# Power_logger_diy_current_voltage_sensors.net
KiCad netlist of a schematic drawn in EasyEDA
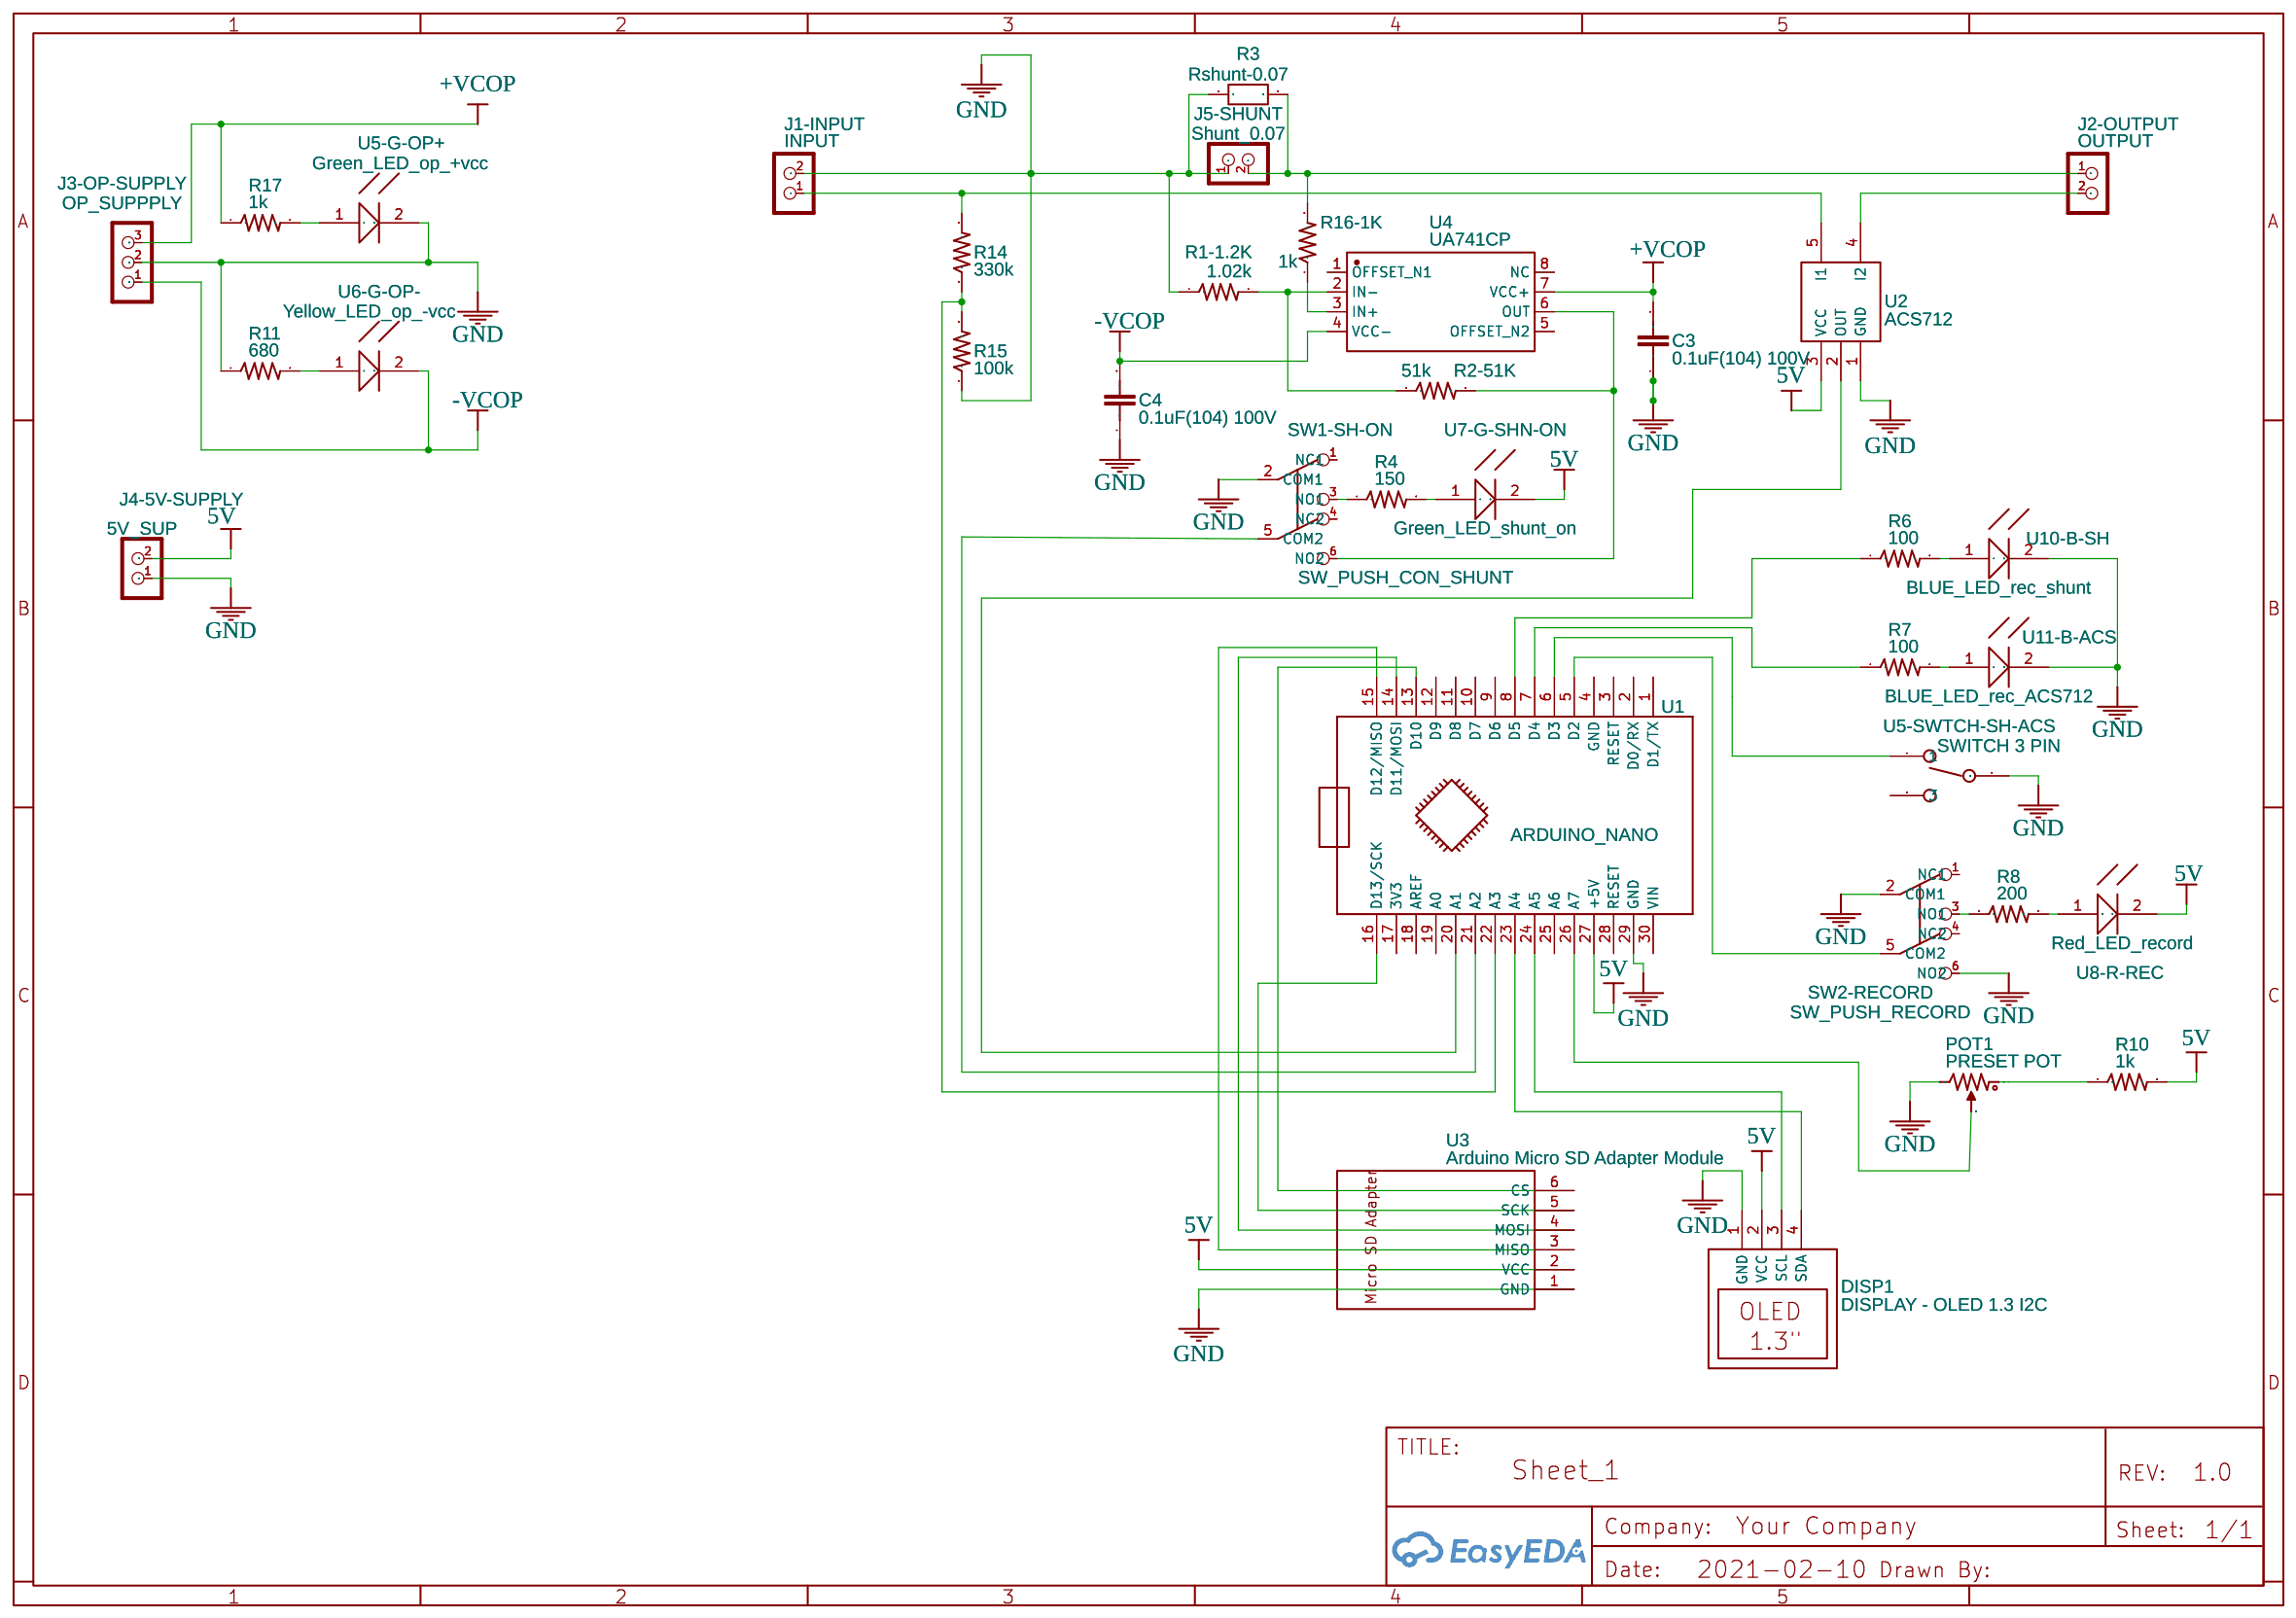
[diagram p0: schematic sheet]

(export (version "E")
  (design (tool "Eeschema 10.0.6"))
  (components
    (comp (ref "C3")
      (value "0.1uF(104) 100V")
      (fields (field (name "BOM_Manufacturer Part") "?"))
      (libsource (lib "") (part "Capacitor Ceramic TH 0.1"))
    )
    (comp (ref "C4")
      (value "0.1uF(104) 100V")
      (fields (field (name "BOM_Manufacturer Part") "?"))
      (libsource (lib "") (part "Capacitor Ceramic TH 0.1"))
    )
    (comp (ref "DISP1") (value "DISPLAY - OLED 1.3 I2C") (libsource (lib "") (part "DISPLAY - OLED 1.3 I2C")))
    (comp (ref "J1-INPUT") (value "INPUT") (libsource (lib "") (part "CON_TERMINAL_BLOCK_02_1")))
    (comp (ref "J2-OUTPUT") (value "OUTPUT") (libsource (lib "") (part "CON_TERMINAL_BLOCK_02_2")))
    (comp (ref "J3-OP-SUPPLY") (value "OP_SUPPPLY") (libsource (lib "") (part "CON_TERMINAL_BLOCK_03")))
    (comp (ref "J4-5V-SUPPLY") (value "5V_SUP") (libsource (lib "") (part "CON_TERMINAL_BLOCK_02_3")))
    (comp (ref "J5-SHUNT") (value "Shunt_0.07") (libsource (lib "") (part "CON_TERMINAL_BLOCK_02")))
    (comp (ref "POT1") (value "PRESET POT") (libsource (lib "") (part "PRESET POT")))
    (comp (ref "R1-1.2K") (value "1.02k") (libsource (lib "") (part "RESISTORKIT_2")))
    (comp (ref "R2-51K") (value "51k") (libsource (lib "") (part "RESISTORKIT_3")))
    (comp (ref "R3") (value "Rshunt-0.07") (libsource (lib "") (part "Res_AXIAL-1.0(3W)_EU")))
    (comp (ref "R4") (value "150") (libsource (lib "") (part "RESISTORKIT")))
    (comp (ref "R6") (value "100") (libsource (lib "") (part "RESISTORKIT")))
    (comp (ref "R7") (value "100") (libsource (lib "") (part "RESISTORKIT")))
    (comp (ref "R8") (value "200") (libsource (lib "") (part "RESISTORKIT")))
    (comp (ref "R10") (value "1k") (libsource (lib "") (part "RESISTORKIT")))
    (comp (ref "R11") (value "680") (libsource (lib "") (part "RESISTORKIT")))
    (comp (ref "R14") (value "330k") (libsource (lib "") (part "RESISTORKIT_1")))
    (comp (ref "R15") (value "100k") (libsource (lib "") (part "RESISTORKIT_1")))
    (comp (ref "R16-1K") (value "1k") (libsource (lib "") (part "RESISTORKIT_4")))
    (comp (ref "R17") (value "1k") (libsource (lib "") (part "RESISTORKIT")))
    (comp (ref "SW1-SH-ON") (value "SW_PUSH_CON_SHUNT") (libsource (lib "") (part "SW_PUSH_DPDT_1")))
    (comp (ref "SW2-RECORD") (value "SW_PUSH_RECORD") (libsource (lib "") (part "SW_PUSH_DPDT")))
    (comp (ref "U1") (value "ARDUINO_NANO") (libsource (lib "") (part "ARDUINO_NANO")))
    (comp (ref "U2") (value "ACS712") (libsource (lib "") (part "ACS712")))
    (comp (ref "U3")
      (value "Arduino Micro SD Adapter Module")
      (libsource (lib "") (part "Arduino Micro SD Adapter Module"))
    )
    (comp (ref "U4")
      (value "UA741CP")
      (fields (field (name "BOM_Supplier Part") "C78758"))
      (libsource (lib "") (part "UA741CP"))
    )
    (comp (ref "U5-G-OP+")
      (value "Green_LED_op_+vcc")
      (fields (field (name "BOM_Manufacturer Part") "703-0090") (field (name "BOM_Supplier Part") "2112100"))
      (libsource (lib "") (part "Red LED"))
    )
    (comp (ref "U5-SWTCH-SH-ACS")
      (value "SWITCH 3 PIN")
      (fields
        (field (name "BOM_Manufacturer Part") "SWITCH")
        (field (name "BOM_Supplier Part") "SWITCH symbol")
      )
      (libsource (lib "") (part "SWITCH 3 PIN"))
    )
    (comp (ref "U6-G-OP-")
      (value "Yellow_LED_op_-vcc")
      (fields (field (name "BOM_Manufacturer Part") "703-0090") (field (name "BOM_Supplier Part") "2112100"))
      (libsource (lib "") (part "Red LED_4"))
    )
    (comp (ref "U7-G-SHN-ON")
      (value "Green_LED_shunt_on")
      (fields (field (name "BOM_Manufacturer Part") "703-0090") (field (name "BOM_Supplier Part") "2112100"))
      (libsource (lib "") (part "Red LED_3"))
    )
    (comp (ref "U8-R-REC")
      (value "Red_LED_record")
      (fields (field (name "BOM_Manufacturer Part") "703-0090") (field (name "BOM_Supplier Part") "2112100"))
      (libsource (lib "") (part "Red LED_1"))
    )
    (comp (ref "U10-B-SH")
      (value "BLUE_LED_rec_shunt")
      (fields (field (name "BOM_Manufacturer Part") "703-0090") (field (name "BOM_Supplier Part") "2112100"))
      (libsource (lib "") (part "Red LED_2"))
    )
    (comp (ref "U11-B-ACS")
      (value "BLUE_LED_rec_ACS712")
      (fields (field (name "BOM_Manufacturer Part") "703-0090") (field (name "BOM_Supplier Part") "2112100"))
      (libsource (lib "") (part "Red LED_5"))
    )
  )
  (nets
    (net (code "1") (name "+VCOP") (class "Default")
      (node (ref "C3") (pin "2") (pinfunction "2_2") (pintype "unspecified"))
      (node (ref "J3-OP-SUPPLY") (pin "3") (pinfunction "3_3") (pintype "unspecified"))
      (node (ref "R17") (pin "1") (pinfunction "1_1") (pintype "unspecified"))
      (node (ref "U4") (pin "7") (pinfunction "VCC+_7") (pintype "unspecified"))
    )
    (net (code "2") (name "-VCOP") (class "Default")
      (node (ref "C4") (pin "2") (pinfunction "2_2") (pintype "unspecified"))
      (node (ref "J3-OP-SUPPLY") (pin "1") (pinfunction "1_1") (pintype "unspecified"))
      (node (ref "U4") (pin "4") (pinfunction "VCC-_4") (pintype "unspecified"))
      (node (ref "U6-G-OP-") (pin "2") (pinfunction "2_2") (pintype "unspecified"))
    )
    (net (code "3") (name "5V") (class "Default")
      (node (ref "DISP1") (pin "2") (pinfunction "VCC_2") (pintype "bidirectional"))
      (node (ref "J4-5V-SUPPLY") (pin "2") (pinfunction "2_2") (pintype "unspecified"))
      (node (ref "R10") (pin "2") (pinfunction "2_2") (pintype "unspecified"))
      (node (ref "U1") (pin "27") (pinfunction "+5V_27") (pintype "unspecified"))
      (node (ref "U2") (pin "3") (pinfunction "VCC_3") (pintype "unspecified"))
      (node (ref "U3") (pin "2") (pinfunction "VCC_2") (pintype "unspecified"))
      (node (ref "U7-G-SHN-ON") (pin "2") (pinfunction "2_2") (pintype "unspecified"))
      (node (ref "U8-R-REC") (pin "2") (pinfunction "2_2") (pintype "unspecified"))
    )
    (net (code "4") (name "GND") (class "Default")
      (node (ref "C3") (pin "1") (pinfunction "1_1") (pintype "unspecified"))
      (node (ref "C4") (pin "1") (pinfunction "1_1") (pintype "unspecified"))
      (node (ref "DISP1") (pin "1") (pinfunction "GND_1") (pintype "bidirectional"))
      (node (ref "J1-INPUT") (pin "2") (pinfunction "2_2") (pintype "unspecified"))
      (node (ref "J3-OP-SUPPLY") (pin "2") (pinfunction "2_2") (pintype "unspecified"))
      (node (ref "J4-5V-SUPPLY") (pin "1") (pinfunction "1_1") (pintype "unspecified"))
      (node (ref "J5-SHUNT") (pin "1") (pinfunction "1_1") (pintype "unspecified"))
      (node (ref "POT1") (pin "3") (pinfunction "3_3") (pintype "unspecified"))
      (node (ref "R1-1.2K") (pin "1") (pinfunction "1_1") (pintype "unspecified"))
      (node (ref "R11") (pin "1") (pinfunction "1_1") (pintype "unspecified"))
      (node (ref "R15") (pin "1") (pinfunction "1_1") (pintype "unspecified"))
      (node (ref "R3") (pin "1") (pinfunction "1_1") (pintype "unspecified"))
      (node (ref "SW1-SH-ON") (pin "2") (pinfunction "COM1_2") (pintype "unspecified"))
      (node (ref "SW2-RECORD") (pin "2") (pinfunction "COM1_2") (pintype "unspecified"))
      (node (ref "SW2-RECORD") (pin "6") (pinfunction "NO2_6") (pintype "unspecified"))
      (node (ref "U1") (pin "29") (pinfunction "GND_29") (pintype "unspecified"))
      (node (ref "U10-B-SH") (pin "2") (pinfunction "2_2") (pintype "unspecified"))
      (node (ref "U11-B-ACS") (pin "2") (pinfunction "2_2") (pintype "unspecified"))
      (node (ref "U2") (pin "1") (pinfunction "GND_1") (pintype "unspecified"))
      (node (ref "U3") (pin "1") (pinfunction "GND_1") (pintype "unspecified"))
      (node (ref "U5-G-OP+") (pin "2") (pinfunction "2_2") (pintype "unspecified"))
      (node (ref "U5-SWTCH-SH-ACS") (pin "2") (pinfunction "2_2") (pintype "unspecified"))
    )
    (net (code "5") (name "Net-(DISP1-SCL)") (class "Default")
      (node (ref "DISP1") (pin "3") (pinfunction "SCL_3") (pintype "passive"))
      (node (ref "U1") (pin "24") (pinfunction "A5_24") (pintype "unspecified"))
    )
    (net (code "6") (name "Net-(DISP1-SDA)") (class "Default")
      (node (ref "DISP1") (pin "4") (pinfunction "SDA_4") (pintype "passive"))
      (node (ref "U1") (pin "23") (pinfunction "A4_23") (pintype "unspecified"))
    )
    (net (code "7") (name "Net-(J2-OUTPUT-Pad1)") (class "Default")
      (node (ref "J2-OUTPUT") (pin "1") (pinfunction "1_1") (pintype "unspecified"))
      (node (ref "J5-SHUNT") (pin "2") (pinfunction "2_2") (pintype "unspecified"))
      (node (ref "R16-1K") (pin "2") (pinfunction "2_2") (pintype "unspecified"))
      (node (ref "R3") (pin "2") (pinfunction "2_2") (pintype "unspecified"))
    )
    (net (code "8") (name "Net-(POT1-Pad1)") (class "Default")
      (node (ref "POT1") (pin "1") (pinfunction "1_1") (pintype "unspecified"))
      (node (ref "R10") (pin "1") (pinfunction "1_1") (pintype "unspecified"))
    )
    (net (code "9") (name "Net-(R4-Pad2)") (class "Default")
      (node (ref "R4") (pin "2") (pinfunction "2_2") (pintype "unspecified"))
      (node (ref "U7-G-SHN-ON") (pin "1") (pinfunction "1_1") (pintype "unspecified"))
    )
    (net (code "10") (name "Net-(R6-Pad2)") (class "Default")
      (node (ref "R6") (pin "2") (pinfunction "2_2") (pintype "unspecified"))
      (node (ref "U10-B-SH") (pin "1") (pinfunction "1_1") (pintype "unspecified"))
    )
    (net (code "11") (name "Net-(R7-Pad2)") (class "Default")
      (node (ref "R7") (pin "2") (pinfunction "2_2") (pintype "unspecified"))
      (node (ref "U11-B-ACS") (pin "1") (pinfunction "1_1") (pintype "unspecified"))
    )
    (net (code "12") (name "Net-(R8-Pad2)") (class "Default")
      (node (ref "R8") (pin "2") (pinfunction "2_2") (pintype "unspecified"))
      (node (ref "U8-R-REC") (pin "1") (pinfunction "1_1") (pintype "unspecified"))
    )
    (net (code "13") (name "Net-(R11-Pad2)") (class "Default")
      (node (ref "R11") (pin "2") (pinfunction "2_2") (pintype "unspecified"))
      (node (ref "U6-G-OP-") (pin "1") (pinfunction "1_1") (pintype "unspecified"))
    )
    (net (code "14") (name "Net-(R17-Pad2)") (class "Default")
      (node (ref "R17") (pin "2") (pinfunction "2_2") (pintype "unspecified"))
      (node (ref "U5-G-OP+") (pin "1") (pinfunction "1_1") (pintype "unspecified"))
    )
    (net (code "15") (name "Net-(SW1-SH-ON-COM2)") (class "Default")
      (node (ref "SW1-SH-ON") (pin "5") (pinfunction "COM2_5") (pintype "unspecified"))
      (node (ref "U1") (pin "21") (pinfunction "A2_21") (pintype "unspecified"))
    )
    (net (code "16") (name "Net-(SW1-SH-ON-NO1)") (class "Default")
      (node (ref "R4") (pin "1") (pinfunction "1_1") (pintype "unspecified"))
      (node (ref "SW1-SH-ON") (pin "3") (pinfunction "NO1_3") (pintype "unspecified"))
    )
    (net (code "17") (name "Net-(SW1-SH-ON-NO2)") (class "Default")
      (node (ref "R2-51K") (pin "2") (pinfunction "2_2") (pintype "unspecified"))
      (node (ref "SW1-SH-ON") (pin "6") (pinfunction "NO2_6") (pintype "unspecified"))
      (node (ref "U4") (pin "6") (pinfunction "OUT_6") (pintype "unspecified"))
    )
    (net (code "18") (name "Net-(SW2-RECORD-COM2)") (class "Default")
      (node (ref "SW2-RECORD") (pin "5") (pinfunction "COM2_5") (pintype "unspecified"))
      (node (ref "U1") (pin "5") (pinfunction "D2_5") (pintype "unspecified"))
    )
    (net (code "19") (name "Net-(SW2-RECORD-NO1)") (class "Default")
      (node (ref "R8") (pin "1") (pinfunction "1_1") (pintype "unspecified"))
      (node (ref "SW2-RECORD") (pin "3") (pinfunction "NO1_3") (pintype "unspecified"))
    )
    (net (code "20") (name "Net-(U1-A1)") (class "Default")
      (node (ref "U1") (pin "20") (pinfunction "A1_20") (pintype "unspecified"))
      (node (ref "U2") (pin "2") (pinfunction "OUT_2") (pintype "unspecified"))
    )
    (net (code "21") (name "Net-(U1-A3)") (class "Default")
      (node (ref "R14") (pin "1") (pinfunction "1_1") (pintype "unspecified"))
      (node (ref "R15") (pin "2") (pinfunction "2_2") (pintype "unspecified"))
      (node (ref "U1") (pin "22") (pinfunction "A3_22") (pintype "unspecified"))
    )
    (net (code "22") (name "Net-(U1-A7)") (class "Default")
      (node (ref "POT1") (pin "2") (pinfunction "2_2") (pintype "unspecified"))
      (node (ref "U1") (pin "26") (pinfunction "A7_26") (pintype "unspecified"))
    )
    (net (code "23") (name "Net-(U1-D3)") (class "Default")
      (node (ref "U1") (pin "6") (pinfunction "D3_6") (pintype "unspecified"))
      (node (ref "U5-SWTCH-SH-ACS") (pin "1") (pinfunction "1_1") (pintype "unspecified"))
    )
    (net (code "24") (name "Net-(U1-D4)") (class "Default")
      (node (ref "R7") (pin "1") (pinfunction "1_1") (pintype "unspecified"))
      (node (ref "U1") (pin "7") (pinfunction "D4_7") (pintype "unspecified"))
    )
    (net (code "25") (name "Net-(U1-D5)") (class "Default")
      (node (ref "R6") (pin "1") (pinfunction "1_1") (pintype "unspecified"))
      (node (ref "U1") (pin "8") (pinfunction "D5_8") (pintype "unspecified"))
    )
    (net (code "26") (name "Net-(U1-D10)") (class "Default")
      (node (ref "U1") (pin "13") (pinfunction "D10_13") (pintype "unspecified"))
      (node (ref "U3") (pin "6") (pinfunction "CS_6") (pintype "unspecified"))
    )
    (net (code "27") (name "Net-(U1-D11{slash}MOSI)") (class "Default")
      (node (ref "U1") (pin "14") (pinfunction "D11/MOSI_14") (pintype "unspecified"))
      (node (ref "U3") (pin "4") (pinfunction "MOSI_4") (pintype "unspecified"))
    )
    (net (code "28") (name "Net-(U1-D12{slash}MISO)") (class "Default")
      (node (ref "U1") (pin "15") (pinfunction "D12/MISO_15") (pintype "unspecified"))
      (node (ref "U3") (pin "3") (pinfunction "MISO_3") (pintype "unspecified"))
    )
    (net (code "29") (name "Net-(U1-D13{slash}SCK)") (class "Default")
      (node (ref "U1") (pin "16") (pinfunction "D13/SCK_16") (pintype "unspecified"))
      (node (ref "U3") (pin "5") (pinfunction "SCK_5") (pintype "unspecified"))
    )
    (net (code "30") (name "Net-(U2-I1)") (class "Default")
      (node (ref "J1-INPUT") (pin "1") (pinfunction "1_1") (pintype "unspecified"))
      (node (ref "R14") (pin "2") (pinfunction "2_2") (pintype "unspecified"))
      (node (ref "U2") (pin "5") (pinfunction "I1_5") (pintype "unspecified"))
    )
    (net (code "31") (name "Net-(U2-I2)") (class "Default")
      (node (ref "J2-OUTPUT") (pin "2") (pinfunction "2_2") (pintype "unspecified"))
      (node (ref "U2") (pin "4") (pinfunction "I2_4") (pintype "unspecified"))
    )
    (net (code "32") (name "Net-(U4-IN+)") (class "Default")
      (node (ref "R16-1K") (pin "1") (pinfunction "1_1") (pintype "unspecified"))
      (node (ref "U4") (pin "3") (pinfunction "IN+_3") (pintype "unspecified"))
    )
    (net (code "33") (name "Net-(U4-IN-)") (class "Default")
      (node (ref "R1-1.2K") (pin "2") (pinfunction "2_2") (pintype "unspecified"))
      (node (ref "R2-51K") (pin "1") (pinfunction "1_1") (pintype "unspecified"))
      (node (ref "U4") (pin "2") (pinfunction "IN-_2") (pintype "unspecified"))
    )
    (net (code "34") (name "unconnected-(SW1-SH-ON-NC1-Pad1)") (class "Default")
      (node (ref "SW1-SH-ON") (pin "1") (pinfunction "NC1_1") (pintype "unspecified"))
    )
    (net (code "35") (name "unconnected-(SW1-SH-ON-NC2-Pad4)") (class "Default")
      (node (ref "SW1-SH-ON") (pin "4") (pinfunction "NC2_4") (pintype "unspecified"))
    )
    (net (code "36") (name "unconnected-(SW2-RECORD-NC1-Pad1)") (class "Default")
      (node (ref "SW2-RECORD") (pin "1") (pinfunction "NC1_1") (pintype "unspecified"))
    )
    (net (code "37") (name "unconnected-(SW2-RECORD-NC2-Pad4)") (class "Default")
      (node (ref "SW2-RECORD") (pin "4") (pinfunction "NC2_4") (pintype "unspecified"))
    )
    (net (code "38") (name "unconnected-(U1-3V3-Pad17)") (class "Default")
      (node (ref "U1") (pin "17") (pinfunction "3V3_17") (pintype "unspecified"))
    )
    (net (code "39") (name "unconnected-(U1-A0-Pad19)") (class "Default")
      (node (ref "U1") (pin "19") (pinfunction "A0_19") (pintype "unspecified"))
    )
    (net (code "40") (name "unconnected-(U1-A6-Pad25)") (class "Default")
      (node (ref "U1") (pin "25") (pinfunction "A6_25") (pintype "unspecified"))
    )
    (net (code "41") (name "unconnected-(U1-AREF-Pad18)") (class "Default")
      (node (ref "U1") (pin "18") (pinfunction "AREF_18") (pintype "unspecified"))
    )
    (net (code "42") (name "unconnected-(U1-D0{slash}RX-Pad2)") (class "Default")
      (node (ref "U1") (pin "2") (pinfunction "D0/RX_2") (pintype "unspecified"))
    )
    (net (code "43") (name "unconnected-(U1-D1{slash}TX-Pad1)") (class "Default")
      (node (ref "U1") (pin "1") (pinfunction "D1/TX_1") (pintype "unspecified"))
    )
    (net (code "44") (name "unconnected-(U1-D6-Pad9)") (class "Default")
      (node (ref "U1") (pin "9") (pinfunction "D6_9") (pintype "unspecified"))
    )
    (net (code "45") (name "unconnected-(U1-D7-Pad10)") (class "Default")
      (node (ref "U1") (pin "10") (pinfunction "D7_10") (pintype "unspecified"))
    )
    (net (code "46") (name "unconnected-(U1-D8-Pad11)") (class "Default")
      (node (ref "U1") (pin "11") (pinfunction "D8_11") (pintype "unspecified"))
    )
    (net (code "47") (name "unconnected-(U1-D9-Pad12)") (class "Default")
      (node (ref "U1") (pin "12") (pinfunction "D9_12") (pintype "unspecified"))
    )
    (net (code "48") (name "unconnected-(U1-GND-Pad4)") (class "Default")
      (node (ref "U1") (pin "4") (pinfunction "GND_4") (pintype "unspecified"))
    )
    (net (code "49") (name "unconnected-(U1-RESET-Pad3)") (class "Default")
      (node (ref "U1") (pin "3") (pinfunction "RESET_3") (pintype "unspecified"))
    )
    (net (code "50") (name "unconnected-(U1-RESET-Pad28)") (class "Default")
      (node (ref "U1") (pin "28") (pinfunction "RESET_28") (pintype "unspecified"))
    )
    (net (code "51") (name "unconnected-(U1-VIN-Pad30)") (class "Default")
      (node (ref "U1") (pin "30") (pinfunction "VIN_30") (pintype "unspecified"))
    )
    (net (code "52") (name "unconnected-(U4-NC-Pad8)") (class "Default")
      (node (ref "U4") (pin "8") (pinfunction "NC_8") (pintype "unspecified"))
    )
    (net (code "53") (name "unconnected-(U4-OFFSET_N1-Pad1)") (class "Default")
      (node (ref "U4") (pin "1") (pinfunction "OFFSET_N1_1") (pintype "unspecified"))
    )
    (net (code "54") (name "unconnected-(U4-OFFSET_N2-Pad5)") (class "Default")
      (node (ref "U4") (pin "5") (pinfunction "OFFSET_N2_5") (pintype "unspecified"))
    )
    (net (code "55") (name "unconnected-(U5-SWTCH-SH-ACS-Pad3)") (class "Default")
      (node (ref "U5-SWTCH-SH-ACS") (pin "3") (pinfunction "3_3") (pintype "unspecified"))
    )
  )
)
